# ADCModule.net
KiCad netlist of a schematic drawn in EAGLE
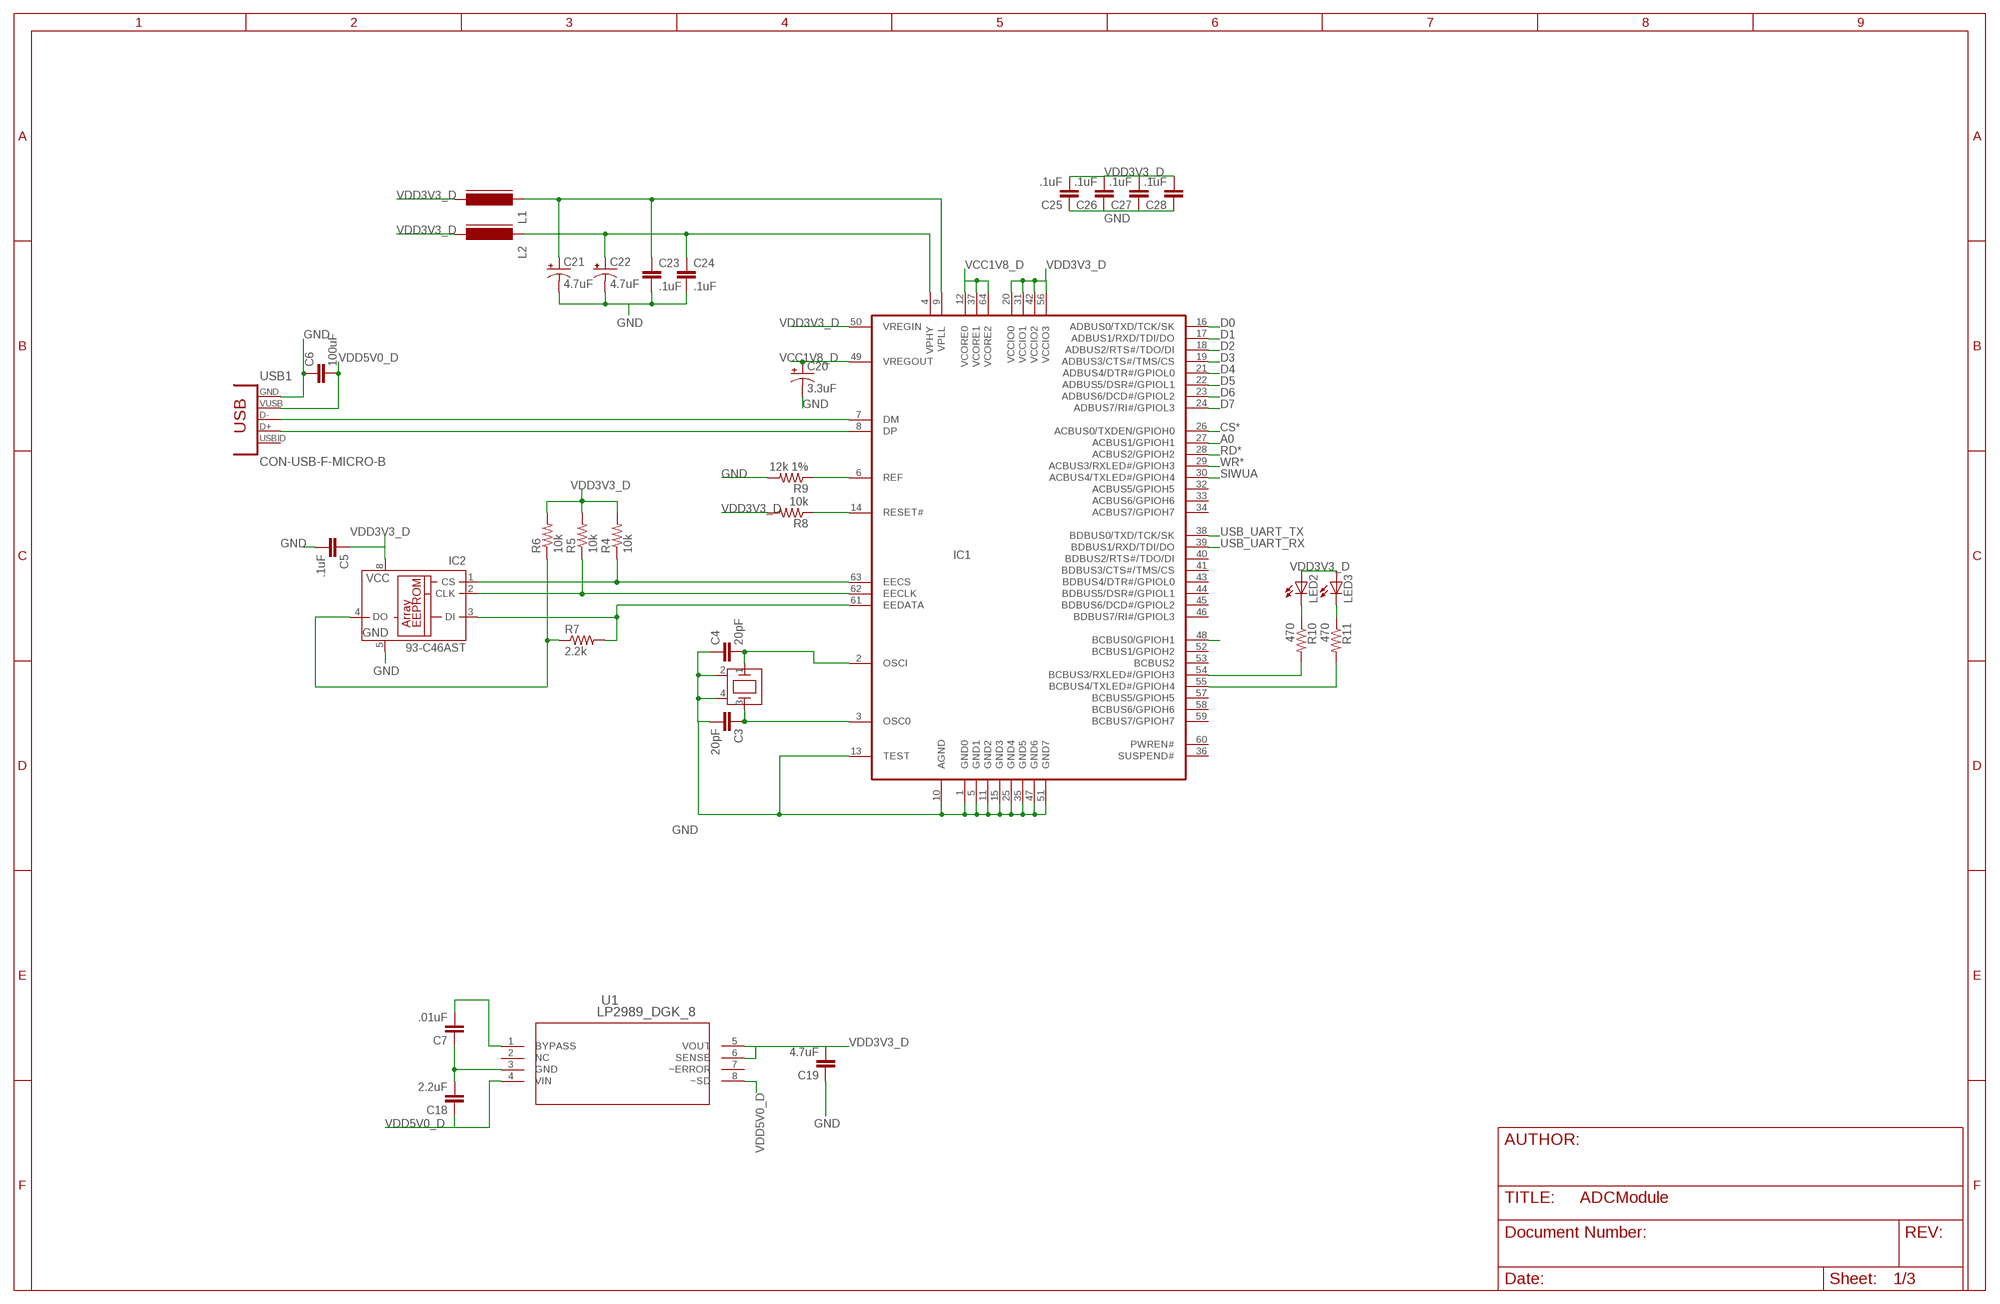
[diagram p0: schematic, sheet 1]
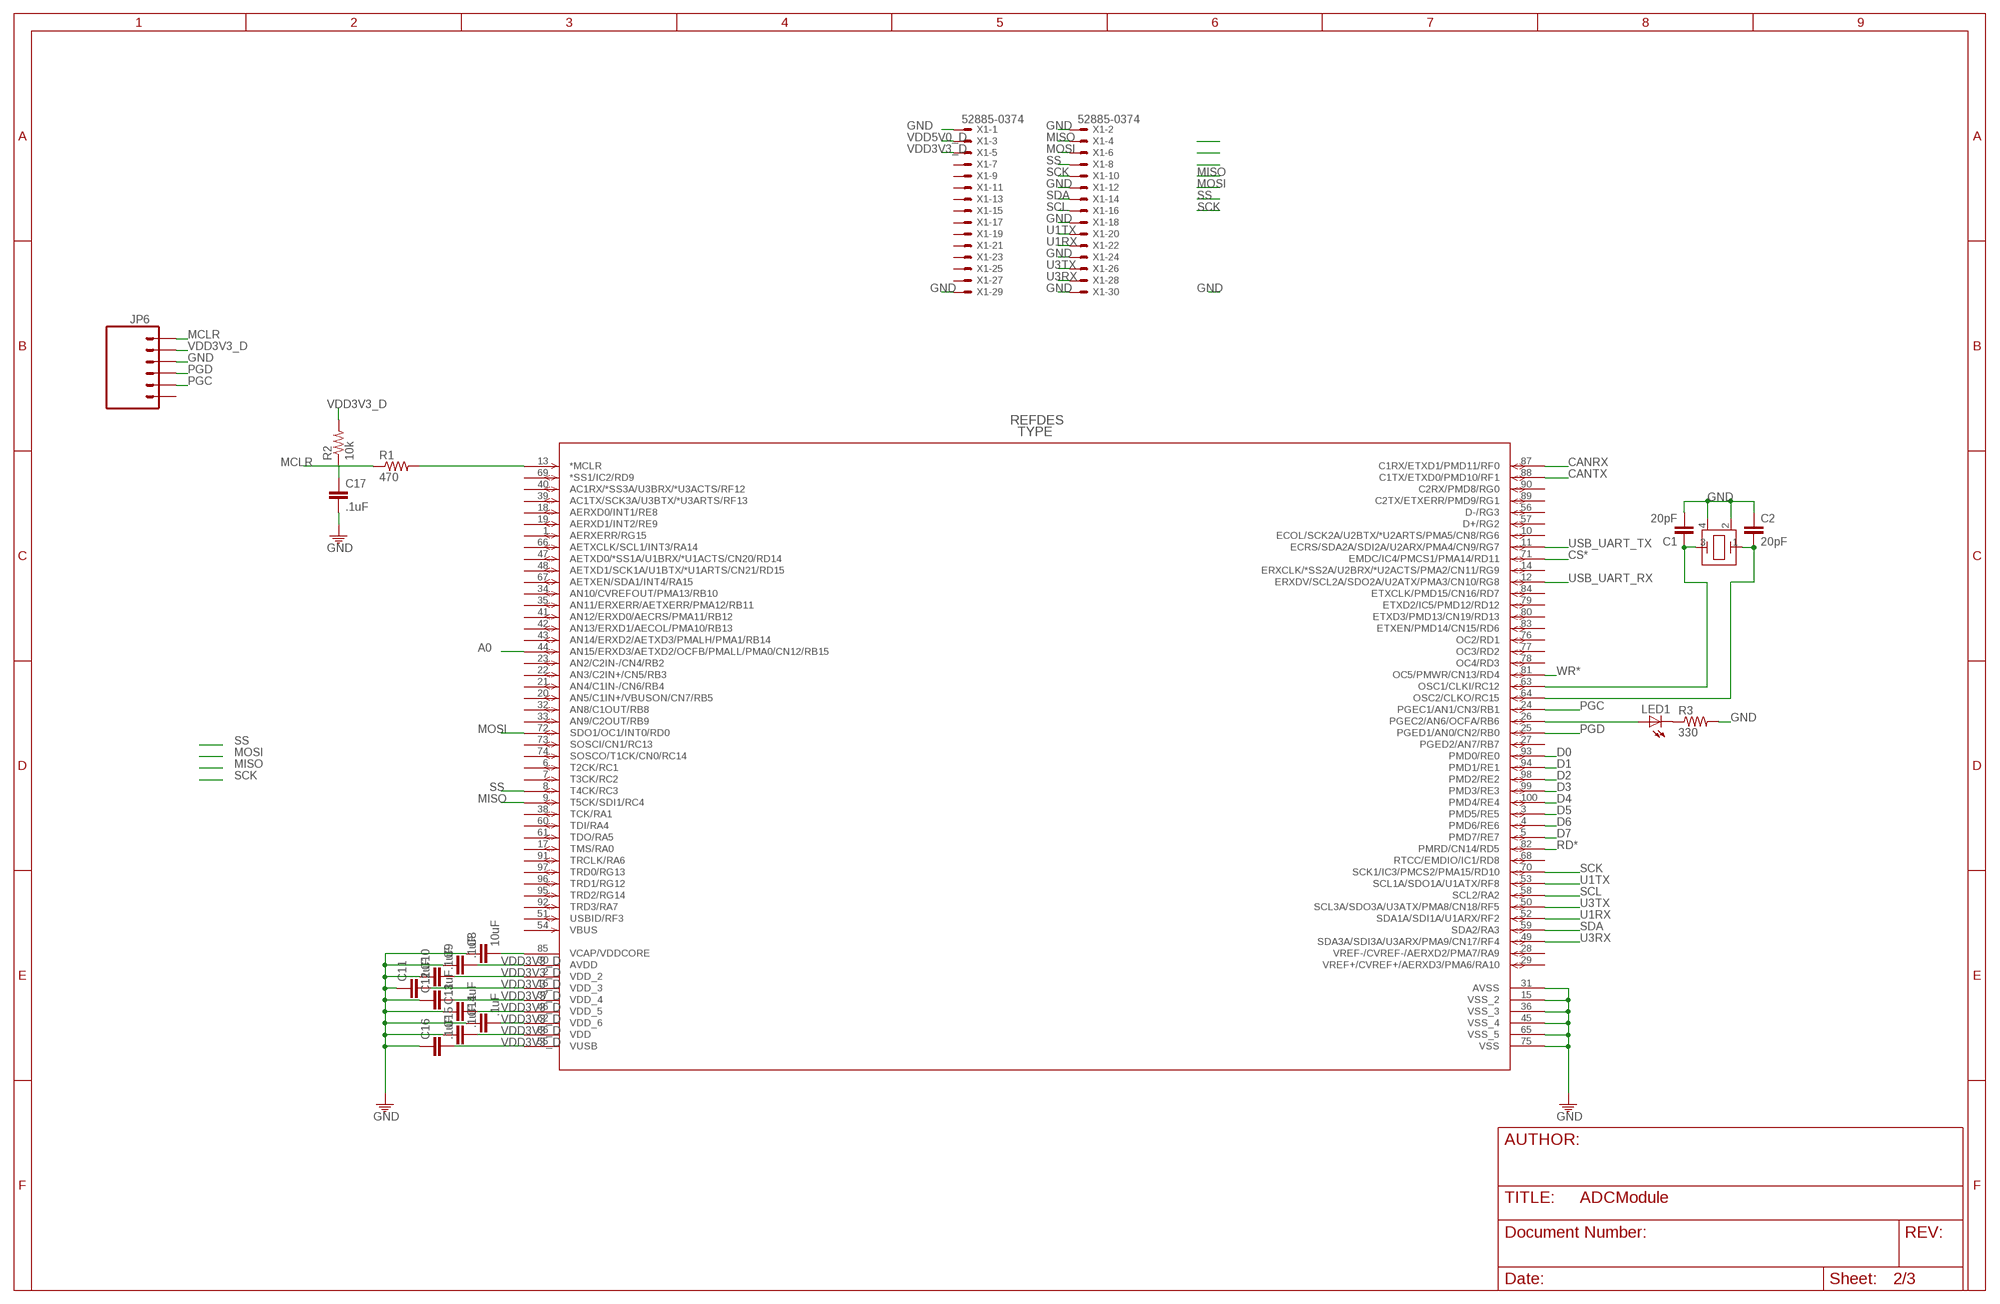
[diagram p1: schematic, sheet 2]
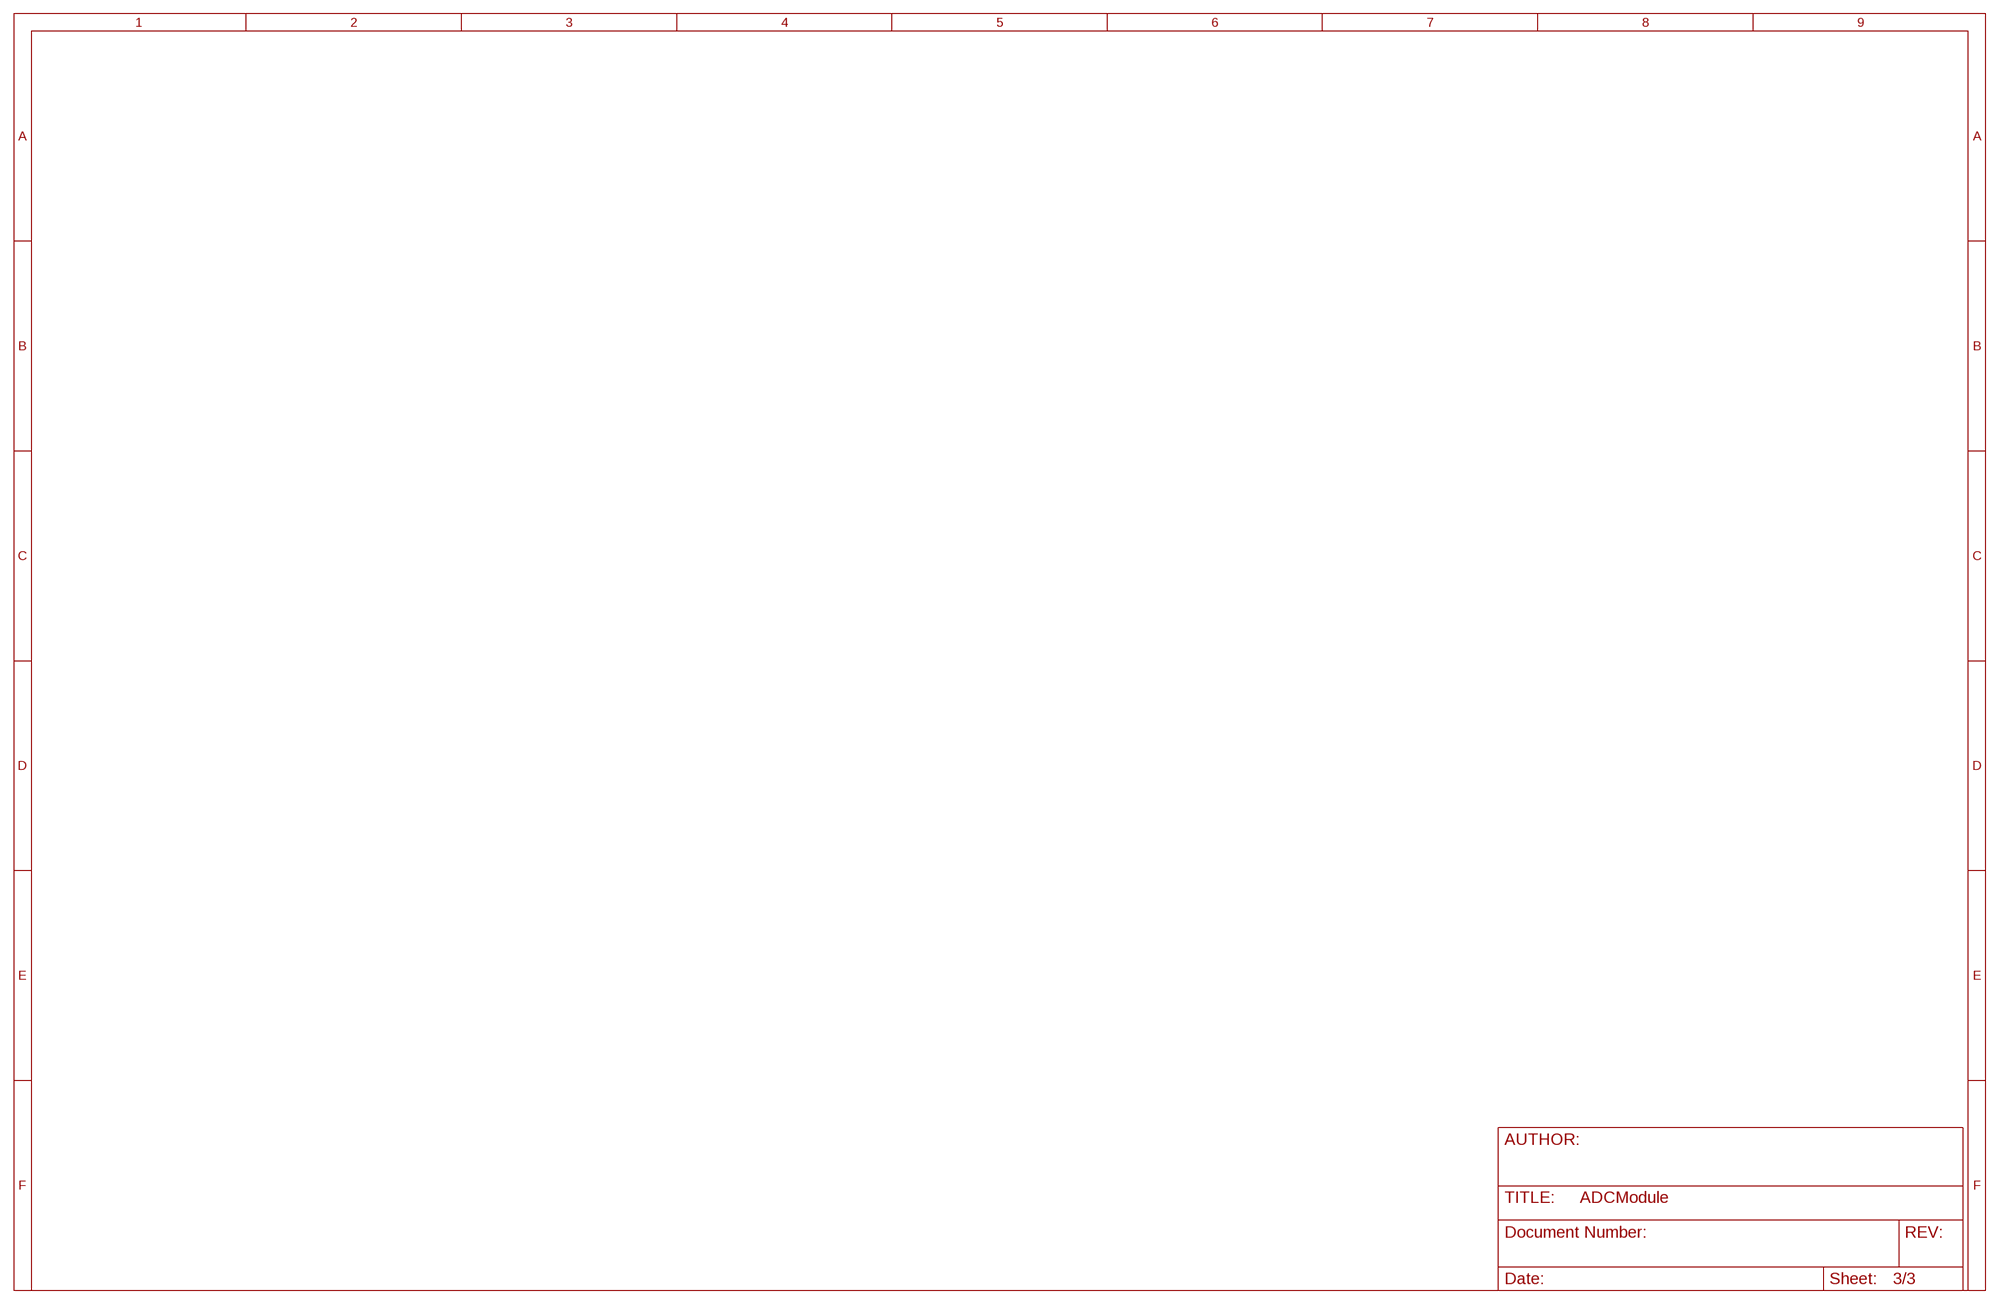
[diagram p2: schematic, sheet 3]

(export (version "E")
  (design (tool "Eeschema 10.0.6"))
  (components
    (comp (ref "C3")
      (value "20pF")
      (footprint "eagle-import:0805")
      (libsource (lib "eagle-import") (part "CAP0805"))
    )
    (comp (ref "C4")
      (value "20pF")
      (footprint "eagle-import:0805")
      (libsource (lib "eagle-import") (part "CAP0805"))
    )
    (comp (ref "C5")
      (value ".1uF")
      (footprint "eagle-import:0805")
      (libsource (lib "eagle-import") (part "CAP0805"))
    )
    (comp (ref "C6")
      (value "100uF")
      (footprint "eagle-import:1206")
      (libsource (lib "eagle-import") (part "CAP1206"))
    )
    (comp (ref "C7")
      (value ".01uF")
      (footprint "eagle-import:0805")
      (libsource (lib "eagle-import") (part "CAP0805"))
    )
    (comp (ref "C18")
      (value "2.2uF")
      (footprint "eagle-import:0805")
      (libsource (lib "eagle-import") (part "CAP0805"))
    )
    (comp (ref "C19")
      (value "4.7uF")
      (footprint "eagle-import:0805")
      (libsource (lib "eagle-import") (part "CAP0805"))
    )
    (comp (ref "C20")
      (value "3.3uF")
      (footprint "eagle-import:EIA3216")
      (libsource (lib "eagle-import") (part "CAP_POL1206"))
    )
    (comp (ref "C21")
      (value "4.7uF")
      (footprint "eagle-import:EIA3216")
      (libsource (lib "eagle-import") (part "CAP_POL1206"))
    )
    (comp (ref "C22")
      (value "4.7uF")
      (footprint "eagle-import:EIA3216")
      (libsource (lib "eagle-import") (part "CAP_POL1206"))
    )
    (comp (ref "C23")
      (value ".1uF")
      (footprint "eagle-import:0805")
      (libsource (lib "eagle-import") (part "CAP0805"))
    )
    (comp (ref "C24")
      (value ".1uF")
      (footprint "eagle-import:0805")
      (libsource (lib "eagle-import") (part "CAP0805"))
    )
    (comp (ref "C25")
      (value ".1uF")
      (footprint "eagle-import:0805")
      (libsource (lib "eagle-import") (part "CAP0805"))
    )
    (comp (ref "C26")
      (value ".1uF")
      (footprint "eagle-import:0805")
      (libsource (lib "eagle-import") (part "CAP0805"))
    )
    (comp (ref "C27")
      (value ".1uF")
      (footprint "eagle-import:0805")
      (libsource (lib "eagle-import") (part "CAP0805"))
    )
    (comp (ref "C28")
      (value ".1uF")
      (footprint "eagle-import:0805")
      (libsource (lib "eagle-import") (part "CAP0805"))
    )
    (comp (ref "IC1")
      (value "IC_FT2232H")
      (footprint "eagle-import:LQFP64")
      (libsource (lib "eagle-import") (part "IC_FT2232H"))
    )
    (comp (ref "IC2")
      (value "93-C46AST")
      (footprint "eagle-import:TSSOP8")
      (fields (field (name "MPN") "CAT93C46YI-G"))
      (libsource (lib "eagle-import") (part "93-STC46A"))
    )
    (comp (ref "L1")
      (value "FERRITE-0805")
      (footprint "eagle-import:FB805")
      (libsource (lib "eagle-import") (part "FERRITE-0805"))
    )
    (comp (ref "L2")
      (value "FERRITE-0805")
      (footprint "eagle-import:FB805")
      (libsource (lib "eagle-import") (part "FERRITE-0805"))
    )
    (comp (ref "LED2")
      (value "LEDCHIP-LED0805")
      (footprint "eagle-import:CHIP-LED0805")
      (libsource (lib "eagle-import") (part "LEDCHIP-LED0805"))
    )
    (comp (ref "LED3")
      (value "LEDCHIP-LED0805")
      (footprint "eagle-import:CHIP-LED0805")
      (libsource (lib "eagle-import") (part "LEDCHIP-LED0805"))
    )
    (comp (ref "R4")
      (value "10k")
      (footprint "eagle-import:0805")
      (libsource (lib "eagle-import") (part "RESISTOR0805-RES"))
    )
    (comp (ref "R5")
      (value "10k")
      (footprint "eagle-import:0805")
      (libsource (lib "eagle-import") (part "RESISTOR0805-RES"))
    )
    (comp (ref "R6")
      (value "10k")
      (footprint "eagle-import:0805")
      (libsource (lib "eagle-import") (part "RESISTOR0805-RES"))
    )
    (comp (ref "R7")
      (value "2.2k")
      (footprint "eagle-import:0805")
      (libsource (lib "eagle-import") (part "RESISTOR0805-RES"))
    )
    (comp (ref "R8")
      (value "10k")
      (footprint "eagle-import:0805")
      (libsource (lib "eagle-import") (part "RESISTOR0805-RES"))
    )
    (comp (ref "R9")
      (value "12k 1%")
      (footprint "eagle-import:0805")
      (libsource (lib "eagle-import") (part "RESISTOR0805-RES"))
    )
    (comp (ref "R10")
      (value "470")
      (footprint "eagle-import:0805")
      (libsource (lib "eagle-import") (part "RESISTOR0805-RES"))
    )
    (comp (ref "R11")
      (value "470")
      (footprint "eagle-import:0805")
      (libsource (lib "eagle-import") (part "RESISTOR0805-RES"))
    )
    (comp (ref "U$3")
      (value "7M-12.000MEEQ-T")
      (footprint "eagle-import:7M-CRYSTAL")
      (libsource (lib "eagle-import") (part "7M-12.000MEEQ-T"))
    )
    (comp (ref "U1")
      (value "LP2989_DGK_8")
      (footprint "eagle-import:MUA08A")
      (fields (field (name "PARTNUMBER") "LP2989AIMM-25"))
      (libsource (lib "eagle-import") (part "LP2989_DGK_8"))
    )
    (comp (ref "USB1")
      (value "CON-USB-F-MICRO-B")
      (footprint "eagle-import:CONN_USB_MICRO-B")
      (libsource (lib "eagle-import") (part "CON-USB-F-MICRO-B"))
    )
    (comp (ref "C1")
      (value "20pF")
      (footprint "eagle-import:0805")
      (libsource (lib "eagle-import") (part "CAP0805"))
    )
    (comp (ref "C2")
      (value "20pF")
      (footprint "eagle-import:0805")
      (libsource (lib "eagle-import") (part "CAP0805"))
    )
    (comp (ref "C8")
      (value "10uF")
      (footprint "eagle-import:0805")
      (libsource (lib "eagle-import") (part "CAP0805"))
    )
    (comp (ref "C9")
      (value ".1uF")
      (footprint "eagle-import:0805")
      (libsource (lib "eagle-import") (part "CAP0805"))
    )
    (comp (ref "C10")
      (value ".1uF")
      (footprint "eagle-import:0805")
      (libsource (lib "eagle-import") (part "CAP0805"))
    )
    (comp (ref "C11")
      (value ".1uF")
      (footprint "eagle-import:0805")
      (libsource (lib "eagle-import") (part "CAP0805"))
    )
    (comp (ref "C12")
      (value ".1uF")
      (footprint "eagle-import:0805")
      (libsource (lib "eagle-import") (part "CAP0805"))
    )
    (comp (ref "C13")
      (value ".1uF")
      (footprint "eagle-import:0805")
      (libsource (lib "eagle-import") (part "CAP0805"))
    )
    (comp (ref "C14")
      (value ".1uF")
      (footprint "eagle-import:0805")
      (libsource (lib "eagle-import") (part "CAP0805"))
    )
    (comp (ref "C15")
      (value ".1uF")
      (footprint "eagle-import:0805")
      (libsource (lib "eagle-import") (part "CAP0805"))
    )
    (comp (ref "C16")
      (value ".1uF")
      (footprint "eagle-import:0805")
      (libsource (lib "eagle-import") (part "CAP0805"))
    )
    (comp (ref "C17")
      (value ".1uF")
      (footprint "eagle-import:0805")
      (libsource (lib "eagle-import") (part "CAP0805"))
    )
    (comp (ref "JP6")
      (value "M06SIP_LOCK")
      (footprint "eagle-import:1X06-SIP_LOCK")
      (libsource (lib "eagle-import") (part "M06SIP_LOCK"))
    )
    (comp (ref "LED1")
      (value "LED0805")
      (footprint "eagle-import:LED-0805")
      (libsource (lib "eagle-import") (part "LED0805"))
    )
    (comp (ref "R1")
      (value "470")
      (footprint "eagle-import:0805")
      (libsource (lib "eagle-import") (part "RESISTOR0805-RES"))
    )
    (comp (ref "R2")
      (value "10k")
      (footprint "eagle-import:0805")
      (libsource (lib "eagle-import") (part "RESISTOR0805-RES"))
    )
    (comp (ref "R3")
      (value "330")
      (footprint "eagle-import:0805")
      (libsource (lib "eagle-import") (part "RESISTOR0805-RES"))
    )
    (comp (ref "U$1")
      (value "PIC32MX795F512L-")
      (footprint "eagle-import:TQFP100_12X12MC")
      (libsource (lib "eagle-import") (part "PIC32MX795F512L-"))
    )
    (comp (ref "U$2")
      (value "ABM3B-8.000MHZ-10-1-U-T")
      (footprint "eagle-import:ABM3B")
      (libsource (lib "eagle-import") (part "ABM3B-8.000MHZ-10-1-U-T"))
    )
    (comp (ref "X1")
      (value "52885-0374")
      (footprint "eagle-import:52885-0374")
      (fields (field (name "MPN") "52760-0379"))
      (libsource (lib "eagle-import") (part "52885-0374"))
    )
  )
  (nets
    (net (code "1") (name "A0") (class "Default")
      (node (ref "IC1") (pin "27") (pinfunction "ACBUS1/GPIOH1_27") (pintype "bidirectional"))
      (node (ref "U$1") (pin "44") (pinfunction "AN15/ERXD3/AETXD2/OCFB/PMALL/PMA0/CN12/RB15_44") (pintype "passive"))
    )
    (net (code "2") (name "CANRX") (class "Default")
      (node (ref "U$1") (pin "87") (pinfunction "C1RX/ETXD1/PMD11/RF0_87") (pintype "passive"))
    )
    (net (code "3") (name "CANTX") (class "Default")
      (node (ref "U$1") (pin "88") (pinfunction "C1TX/ETXD0/PMD10/RF1_88") (pintype "passive"))
    )
    (net (code "4") (name "CS*") (class "Default")
      (node (ref "IC1") (pin "26") (pinfunction "ACBUS0/TXDEN/GPIOH0_26") (pintype "bidirectional"))
      (node (ref "U$1") (pin "71") (pinfunction "EMDC/IC4/PMCS1/PMA14/RD11_71") (pintype "passive"))
    )
    (net (code "5") (name "D0") (class "Default")
      (node (ref "IC1") (pin "16") (pinfunction "ADBUS0/TXD/TCK/SK_16") (pintype "bidirectional"))
      (node (ref "U$1") (pin "93") (pinfunction "PMD0/RE0_93") (pintype "passive"))
    )
    (net (code "6") (name "D1") (class "Default")
      (node (ref "IC1") (pin "17") (pinfunction "ADBUS1/RXD/TDI/DO_17") (pintype "bidirectional"))
      (node (ref "U$1") (pin "94") (pinfunction "PMD1/RE1_94") (pintype "passive"))
    )
    (net (code "7") (name "D2") (class "Default")
      (node (ref "IC1") (pin "18") (pinfunction "ADBUS2/RTS#/TDO/DI_18") (pintype "bidirectional"))
      (node (ref "U$1") (pin "98") (pinfunction "PMD2/RE2_98") (pintype "passive"))
    )
    (net (code "8") (name "D3") (class "Default")
      (node (ref "IC1") (pin "19") (pinfunction "ADBUS3/CTS#/TMS/CS_19") (pintype "bidirectional"))
      (node (ref "U$1") (pin "99") (pinfunction "PMD3/RE3_99") (pintype "passive"))
    )
    (net (code "9") (name "D4") (class "Default")
      (node (ref "IC1") (pin "21") (pinfunction "ADBUS4/DTR#/GPIOL0_21") (pintype "bidirectional"))
      (node (ref "U$1") (pin "100") (pinfunction "PMD4/RE4_100") (pintype "passive"))
    )
    (net (code "10") (name "D5") (class "Default")
      (node (ref "IC1") (pin "22") (pinfunction "ADBUS5/DSR#/GPIOL1_22") (pintype "bidirectional"))
      (node (ref "U$1") (pin "3") (pinfunction "PMD5/RE5_3") (pintype "passive"))
    )
    (net (code "11") (name "D6") (class "Default")
      (node (ref "IC1") (pin "23") (pinfunction "ADBUS6/DCD#/GPIOL2_23") (pintype "bidirectional"))
      (node (ref "U$1") (pin "4") (pinfunction "PMD6/RE6_4") (pintype "passive"))
    )
    (net (code "12") (name "D7") (class "Default")
      (node (ref "IC1") (pin "24") (pinfunction "ADBUS7/RI#/GPIOL3_24") (pintype "bidirectional"))
      (node (ref "U$1") (pin "5") (pinfunction "PMD7/RE7_5") (pintype "passive"))
    )
    (net (code "13") (name "GND") (class "Default")
      (node (ref "C1") (pin "2") (pinfunction "2_2") (pintype "passive"))
      (node (ref "C10") (pin "1") (pinfunction "1_1") (pintype "passive"))
      (node (ref "C11") (pin "1") (pinfunction "1_1") (pintype "passive"))
      (node (ref "C12") (pin "1") (pinfunction "1_1") (pintype "passive"))
      (node (ref "C13") (pin "1") (pinfunction "1_1") (pintype "passive"))
      (node (ref "C14") (pin "1") (pinfunction "1_1") (pintype "passive"))
      (node (ref "C15") (pin "1") (pinfunction "1_1") (pintype "passive"))
      (node (ref "C16") (pin "1") (pinfunction "1_1") (pintype "passive"))
      (node (ref "C17") (pin "2") (pinfunction "2_2") (pintype "passive"))
      (node (ref "C18") (pin "2") (pinfunction "2_2") (pintype "passive"))
      (node (ref "C19") (pin "1") (pinfunction "1_1") (pintype "passive"))
      (node (ref "C2") (pin "1") (pinfunction "1_1") (pintype "passive"))
      (node (ref "C20") (pin "C") (pinfunction "-_C") (pintype "passive"))
      (node (ref "C21") (pin "C") (pinfunction "-_C") (pintype "passive"))
      (node (ref "C22") (pin "C") (pinfunction "-_C") (pintype "passive"))
      (node (ref "C23") (pin "2") (pinfunction "2_2") (pintype "passive"))
      (node (ref "C24") (pin "2") (pinfunction "2_2") (pintype "passive"))
      (node (ref "C25") (pin "1") (pinfunction "1_1") (pintype "passive"))
      (node (ref "C26") (pin "1") (pinfunction "1_1") (pintype "passive"))
      (node (ref "C27") (pin "1") (pinfunction "1_1") (pintype "passive"))
      (node (ref "C28") (pin "1") (pinfunction "1_1") (pintype "passive"))
      (node (ref "C3") (pin "2") (pinfunction "2_2") (pintype "passive"))
      (node (ref "C4") (pin "1") (pinfunction "1_1") (pintype "passive"))
      (node (ref "C5") (pin "2") (pinfunction "2_2") (pintype "passive"))
      (node (ref "C6") (pin "1") (pinfunction "1_1") (pintype "passive"))
      (node (ref "C7") (pin "1") (pinfunction "1_1") (pintype "passive"))
      (node (ref "C8") (pin "1") (pinfunction "1_1") (pintype "passive"))
      (node (ref "C9") (pin "1") (pinfunction "1_1") (pintype "passive"))
      (node (ref "IC1") (pin "1") (pinfunction "GND0_1") (pintype "bidirectional"))
      (node (ref "IC1") (pin "10") (pinfunction "AGND_10") (pintype "bidirectional"))
      (node (ref "IC1") (pin "11") (pinfunction "GND2_11") (pintype "bidirectional"))
      (node (ref "IC1") (pin "13") (pinfunction "TEST_13") (pintype "bidirectional"))
      (node (ref "IC1") (pin "15") (pinfunction "GND3_15") (pintype "bidirectional"))
      (node (ref "IC1") (pin "25") (pinfunction "GND4_25") (pintype "bidirectional"))
      (node (ref "IC1") (pin "35") (pinfunction "GND5_35") (pintype "bidirectional"))
      (node (ref "IC1") (pin "47") (pinfunction "GND6_47") (pintype "bidirectional"))
      (node (ref "IC1") (pin "5") (pinfunction "GND1_5") (pintype "bidirectional"))
      (node (ref "IC1") (pin "51") (pinfunction "GND7_51") (pintype "bidirectional"))
      (node (ref "IC2") (pin "5") (pinfunction "GND_5") (pintype "power_in"))
      (node (ref "JP6") (pin "3") (pinfunction "3_3") (pintype "passive"))
      (node (ref "R3") (pin "2") (pinfunction "2_2") (pintype "passive"))
      (node (ref "R9") (pin "2") (pinfunction "2_2") (pintype "passive"))
      (node (ref "U$1") (pin "15") (pinfunction "VSS_2_15") (pintype "passive"))
      (node (ref "U$1") (pin "31") (pinfunction "AVSS_31") (pintype "passive"))
      (node (ref "U$1") (pin "36") (pinfunction "VSS_3_36") (pintype "passive"))
      (node (ref "U$1") (pin "45") (pinfunction "VSS_4_45") (pintype "passive"))
      (node (ref "U$1") (pin "65") (pinfunction "VSS_5_65") (pintype "passive"))
      (node (ref "U$1") (pin "75") (pinfunction "VSS_75") (pintype "passive"))
      (node (ref "U$2") (pin "2") (pinfunction "GND1_2") (pintype "bidirectional"))
      (node (ref "U$2") (pin "4") (pinfunction "GND2_4") (pintype "bidirectional"))
      (node (ref "U$3") (pin "2") (pinfunction "GND1_2") (pintype "bidirectional"))
      (node (ref "U$3") (pin "4") (pinfunction "GND2_4") (pintype "bidirectional"))
      (node (ref "U1") (pin "3") (pinfunction "GND_3") (pintype "passive"))
      (node (ref "USB1") (pin "P5") (pinfunction "GND_P5") (pintype "bidirectional"))
      (node (ref "X1") (pin "1") (pinfunction "S_1") (pintype "passive"))
      (node (ref "X1") (pin "12") (pinfunction "S_12") (pintype "passive"))
      (node (ref "X1") (pin "18") (pinfunction "S_18") (pintype "passive"))
      (node (ref "X1") (pin "2") (pinfunction "S_2") (pintype "passive"))
      (node (ref "X1") (pin "24") (pinfunction "S_24") (pintype "passive"))
      (node (ref "X1") (pin "29") (pinfunction "S_29") (pintype "passive"))
      (node (ref "X1") (pin "30") (pinfunction "S_30") (pintype "passive"))
    )
    (net (code "14") (name "MCLR") (class "Default")
      (node (ref "C17") (pin "1") (pinfunction "1_1") (pintype "passive"))
      (node (ref "JP6") (pin "1") (pinfunction "1_1") (pintype "passive"))
      (node (ref "R1") (pin "1") (pinfunction "1_1") (pintype "passive"))
      (node (ref "R2") (pin "1") (pinfunction "1_1") (pintype "passive"))
    )
    (net (code "15") (name "MISO") (class "Default")
      (node (ref "U$1") (pin "9") (pinfunction "T5CK/SDI1/RC4_9") (pintype "passive"))
      (node (ref "X1") (pin "4") (pinfunction "S_4") (pintype "passive"))
    )
    (net (code "16") (name "MOSI") (class "Default")
      (node (ref "U$1") (pin "72") (pinfunction "SDO1/OC1/INT0/RD0_72") (pintype "passive"))
      (node (ref "X1") (pin "6") (pinfunction "S_6") (pintype "passive"))
    )
    (net (code "17") (name "Net-(C21-+)") (class "Default")
      (node (ref "C21") (pin "A") (pinfunction "+_A") (pintype "passive"))
      (node (ref "C23") (pin "1") (pinfunction "1_1") (pintype "passive"))
      (node (ref "IC1") (pin "9") (pinfunction "VPLL_9") (pintype "bidirectional"))
      (node (ref "L1") (pin "1") (pinfunction "1_1") (pintype "passive"))
    )
    (net (code "18") (name "Net-(C22-+)") (class "Default")
      (node (ref "C22") (pin "A") (pinfunction "+_A") (pintype "passive"))
      (node (ref "C24") (pin "1") (pinfunction "1_1") (pintype "passive"))
      (node (ref "IC1") (pin "4") (pinfunction "VPHY_4") (pintype "bidirectional"))
      (node (ref "L2") (pin "1") (pinfunction "1_1") (pintype "passive"))
    )
    (net (code "19") (name "Net-(IC1-BCBUS3{slash}RXLED#{slash}GPIOH3)") (class "Default")
      (node (ref "IC1") (pin "54") (pinfunction "BCBUS3/RXLED#/GPIOH3_54") (pintype "bidirectional"))
      (node (ref "R10") (pin "2") (pinfunction "2_2") (pintype "passive"))
    )
    (net (code "20") (name "Net-(IC1-BCBUS4{slash}TXLED#{slash}GPIOH4)") (class "Default")
      (node (ref "IC1") (pin "55") (pinfunction "BCBUS4/TXLED#/GPIOH4_55") (pintype "bidirectional"))
      (node (ref "R11") (pin "2") (pinfunction "2_2") (pintype "passive"))
    )
    (net (code "21") (name "Net-(IC1-DM)") (class "Default")
      (node (ref "IC1") (pin "7") (pinfunction "DM_7") (pintype "bidirectional"))
      (node (ref "USB1") (pin "P2") (pinfunction "D-_P2") (pintype "bidirectional"))
    )
    (net (code "22") (name "Net-(IC1-DP)") (class "Default")
      (node (ref "IC1") (pin "8") (pinfunction "DP_8") (pintype "bidirectional"))
      (node (ref "USB1") (pin "P3") (pinfunction "D+_P3") (pintype "bidirectional"))
    )
    (net (code "23") (name "Net-(IC1-EECLK)") (class "Default")
      (node (ref "IC1") (pin "62") (pinfunction "EECLK_62") (pintype "bidirectional"))
      (node (ref "IC2") (pin "2") (pinfunction "CLK_2") (pintype "input"))
      (node (ref "R5") (pin "1") (pinfunction "1_1") (pintype "passive"))
    )
    (net (code "24") (name "Net-(IC1-EECS)") (class "Default")
      (node (ref "IC1") (pin "63") (pinfunction "EECS_63") (pintype "bidirectional"))
      (node (ref "IC2") (pin "1") (pinfunction "CS_1") (pintype "input"))
      (node (ref "R4") (pin "1") (pinfunction "1_1") (pintype "passive"))
    )
    (net (code "25") (name "Net-(IC1-EEDATA)") (class "Default")
      (node (ref "IC1") (pin "61") (pinfunction "EEDATA_61") (pintype "bidirectional"))
      (node (ref "IC2") (pin "3") (pinfunction "DI_3") (pintype "input"))
      (node (ref "R7") (pin "2") (pinfunction "2_2") (pintype "passive"))
    )
    (net (code "26") (name "Net-(IC1-OSC0)") (class "Default")
      (node (ref "C3") (pin "1") (pinfunction "1_1") (pintype "passive"))
      (node (ref "IC1") (pin "3") (pinfunction "OSC0_3") (pintype "bidirectional"))
      (node (ref "U$3") (pin "3") (pinfunction "OSC2_3") (pintype "bidirectional"))
    )
    (net (code "27") (name "Net-(IC1-OSCI)") (class "Default")
      (node (ref "C4") (pin "2") (pinfunction "2_2") (pintype "passive"))
      (node (ref "IC1") (pin "2") (pinfunction "OSCI_2") (pintype "bidirectional"))
      (node (ref "U$3") (pin "1") (pinfunction "OSC1_1") (pintype "bidirectional"))
    )
    (net (code "28") (name "Net-(IC1-REF)") (class "Default")
      (node (ref "IC1") (pin "6") (pinfunction "REF_6") (pintype "bidirectional"))
      (node (ref "R9") (pin "1") (pinfunction "1_1") (pintype "passive"))
    )
    (net (code "29") (name "Net-(IC1-RESET#)") (class "Default")
      (node (ref "IC1") (pin "14") (pinfunction "RESET#_14") (pintype "bidirectional"))
      (node (ref "R8") (pin "1") (pinfunction "1_1") (pintype "passive"))
    )
    (net (code "30") (name "Net-(IC2-DO)") (class "Default")
      (node (ref "IC2") (pin "4") (pinfunction "DO_4") (pintype "tri_state"))
      (node (ref "R6") (pin "1") (pinfunction "1_1") (pintype "passive"))
      (node (ref "R7") (pin "1") (pinfunction "1_1") (pintype "passive"))
    )
    (net (code "31") (name "Net-(LED1-A)") (class "Default")
      (node (ref "LED1") (pin "1") (pinfunction "A_1") (pintype "passive"))
      (node (ref "U$1") (pin "26") (pinfunction "PGEC2/AN6/OCFA/RB6_26") (pintype "passive"))
    )
    (net (code "32") (name "Net-(LED1-C)") (class "Default")
      (node (ref "LED1") (pin "2") (pinfunction "C_2") (pintype "passive"))
      (node (ref "R3") (pin "1") (pinfunction "1_1") (pintype "passive"))
    )
    (net (code "33") (name "Net-(LED2-PadC)") (class "Default")
      (node (ref "LED2") (pin "C") (pinfunction "C_C") (pintype "passive"))
      (node (ref "R10") (pin "1") (pinfunction "1_1") (pintype "passive"))
    )
    (net (code "34") (name "Net-(LED3-PadC)") (class "Default")
      (node (ref "LED3") (pin "C") (pinfunction "C_C") (pintype "passive"))
      (node (ref "R11") (pin "1") (pinfunction "1_1") (pintype "passive"))
    )
    (net (code "35") (name "Net-(U$1-*MCLR)") (class "Default")
      (node (ref "R1") (pin "2") (pinfunction "2_2") (pintype "passive"))
      (node (ref "U$1") (pin "13") (pinfunction "*MCLR_13") (pintype "passive"))
    )
    (net (code "36") (name "Net-(U$1-OSC1{slash}CLKI{slash}RC12)") (class "Default")
      (node (ref "C1") (pin "1") (pinfunction "1_1") (pintype "passive"))
      (node (ref "U$1") (pin "63") (pinfunction "OSC1/CLKI/RC12_63") (pintype "passive"))
      (node (ref "U$2") (pin "3") (pinfunction "OSC2_3") (pintype "bidirectional"))
    )
    (net (code "37") (name "Net-(U$1-OSC2{slash}CLKO{slash}RC15)") (class "Default")
      (node (ref "C2") (pin "2") (pinfunction "2_2") (pintype "passive"))
      (node (ref "U$1") (pin "64") (pinfunction "OSC2/CLKO/RC15_64") (pintype "passive"))
      (node (ref "U$2") (pin "1") (pinfunction "OSC1_1") (pintype "bidirectional"))
    )
    (net (code "38") (name "Net-(U$1-VCAP{slash}VDDCORE)") (class "Default")
      (node (ref "C8") (pin "2") (pinfunction "2_2") (pintype "passive"))
      (node (ref "U$1") (pin "85") (pinfunction "VCAP/VDDCORE_85") (pintype "passive"))
    )
    (net (code "39") (name "Net-(U1-BYPASS)") (class "Default")
      (node (ref "C7") (pin "2") (pinfunction "2_2") (pintype "passive"))
      (node (ref "U1") (pin "1") (pinfunction "BYPASS_1") (pintype "passive"))
    )
    (net (code "40") (name "PGC") (class "Default")
      (node (ref "JP6") (pin "5") (pinfunction "5_5") (pintype "passive"))
      (node (ref "U$1") (pin "24") (pinfunction "PGEC1/AN1/CN3/RB1_24") (pintype "passive"))
    )
    (net (code "41") (name "PGD") (class "Default")
      (node (ref "JP6") (pin "4") (pinfunction "4_4") (pintype "passive"))
      (node (ref "U$1") (pin "25") (pinfunction "PGED1/AN0/CN2/RB0_25") (pintype "passive"))
    )
    (net (code "42") (name "RD*") (class "Default")
      (node (ref "IC1") (pin "28") (pinfunction "ACBUS2/GPIOH2_28") (pintype "bidirectional"))
      (node (ref "U$1") (pin "82") (pinfunction "PMRD/CN14/RD5_82") (pintype "passive"))
    )
    (net (code "43") (name "SCK") (class "Default")
      (node (ref "U$1") (pin "70") (pinfunction "SCK1/IC3/PMCS2/PMA15/RD10_70") (pintype "passive"))
      (node (ref "X1") (pin "10") (pinfunction "S_10") (pintype "passive"))
    )
    (net (code "44") (name "SCL") (class "Default")
      (node (ref "U$1") (pin "58") (pinfunction "SCL2/RA2_58") (pintype "passive"))
      (node (ref "X1") (pin "16") (pinfunction "S_16") (pintype "passive"))
    )
    (net (code "45") (name "SDA") (class "Default")
      (node (ref "U$1") (pin "59") (pinfunction "SDA2/RA3_59") (pintype "passive"))
      (node (ref "X1") (pin "14") (pinfunction "S_14") (pintype "passive"))
    )
    (net (code "46") (name "SIWUA") (class "Default")
      (node (ref "IC1") (pin "30") (pinfunction "ACBUS4/TXLED#/GPIOH4_30") (pintype "bidirectional"))
    )
    (net (code "47") (name "SS") (class "Default")
      (node (ref "U$1") (pin "8") (pinfunction "T4CK/RC3_8") (pintype "passive"))
      (node (ref "X1") (pin "8") (pinfunction "S_8") (pintype "passive"))
    )
    (net (code "48") (name "U1RX") (class "Default")
      (node (ref "U$1") (pin "52") (pinfunction "SDA1A/SDI1A/U1ARX/RF2_52") (pintype "passive"))
      (node (ref "X1") (pin "22") (pinfunction "S_22") (pintype "passive"))
    )
    (net (code "49") (name "U1TX") (class "Default")
      (node (ref "U$1") (pin "53") (pinfunction "SCL1A/SDO1A/U1ATX/RF8_53") (pintype "passive"))
      (node (ref "X1") (pin "20") (pinfunction "S_20") (pintype "passive"))
    )
    (net (code "50") (name "U3RX") (class "Default")
      (node (ref "U$1") (pin "49") (pinfunction "SDA3A/SDI3A/U3ARX/PMA9/CN17/RF4_49") (pintype "passive"))
      (node (ref "X1") (pin "28") (pinfunction "S_28") (pintype "passive"))
    )
    (net (code "51") (name "U3TX") (class "Default")
      (node (ref "U$1") (pin "50") (pinfunction "SCL3A/SDO3A/U3ATX/PMA8/CN18/RF5_50") (pintype "passive"))
      (node (ref "X1") (pin "26") (pinfunction "S_26") (pintype "passive"))
    )
    (net (code "52") (name "USB_UART_RX") (class "Default")
      (node (ref "IC1") (pin "39") (pinfunction "BDBUS1/RXD/TDI/DO_39") (pintype "bidirectional"))
      (node (ref "U$1") (pin "12") (pinfunction "ERXDV/SCL2A/SDO2A/U2ATX/PMA3/CN10/RG8_12") (pintype "passive"))
    )
    (net (code "53") (name "USB_UART_TX") (class "Default")
      (node (ref "IC1") (pin "38") (pinfunction "BDBUS0/TXD/TCK/SK_38") (pintype "bidirectional"))
      (node (ref "U$1") (pin "11") (pinfunction "ECRS/SDA2A/SDI2A/U2ARX/PMA4/CN9/RG7_11") (pintype "passive"))
    )
    (net (code "54") (name "VCC1V8_D") (class "Default")
      (node (ref "C20") (pin "A") (pinfunction "+_A") (pintype "passive"))
      (node (ref "IC1") (pin "12") (pinfunction "VCORE0_12") (pintype "bidirectional"))
      (node (ref "IC1") (pin "37") (pinfunction "VCORE1_37") (pintype "bidirectional"))
      (node (ref "IC1") (pin "49") (pinfunction "VREGOUT_49") (pintype "bidirectional"))
      (node (ref "IC1") (pin "64") (pinfunction "VCORE2_64") (pintype "bidirectional"))
    )
    (net (code "55") (name "VDD3V3_D") (class "Default")
      (node (ref "C10") (pin "2") (pinfunction "2_2") (pintype "passive"))
      (node (ref "C11") (pin "2") (pinfunction "2_2") (pintype "passive"))
      (node (ref "C12") (pin "2") (pinfunction "2_2") (pintype "passive"))
      (node (ref "C13") (pin "2") (pinfunction "2_2") (pintype "passive"))
      (node (ref "C14") (pin "2") (pinfunction "2_2") (pintype "passive"))
      (node (ref "C15") (pin "2") (pinfunction "2_2") (pintype "passive"))
      (node (ref "C16") (pin "2") (pinfunction "2_2") (pintype "passive"))
      (node (ref "C19") (pin "2") (pinfunction "2_2") (pintype "passive"))
      (node (ref "C25") (pin "2") (pinfunction "2_2") (pintype "passive"))
      (node (ref "C26") (pin "2") (pinfunction "2_2") (pintype "passive"))
      (node (ref "C27") (pin "2") (pinfunction "2_2") (pintype "passive"))
      (node (ref "C28") (pin "2") (pinfunction "2_2") (pintype "passive"))
      (node (ref "C5") (pin "1") (pinfunction "1_1") (pintype "passive"))
      (node (ref "C9") (pin "2") (pinfunction "2_2") (pintype "passive"))
      (node (ref "IC1") (pin "20") (pinfunction "VCCIO0_20") (pintype "bidirectional"))
      (node (ref "IC1") (pin "31") (pinfunction "VCCIO1_31") (pintype "bidirectional"))
      (node (ref "IC1") (pin "42") (pinfunction "VCCIO2_42") (pintype "bidirectional"))
      (node (ref "IC1") (pin "50") (pinfunction "VREGIN_50") (pintype "bidirectional"))
      (node (ref "IC1") (pin "56") (pinfunction "VCCIO3_56") (pintype "bidirectional"))
      (node (ref "IC2") (pin "8") (pinfunction "VCC_8") (pintype "power_in"))
      (node (ref "JP6") (pin "2") (pinfunction "2_2") (pintype "passive"))
      (node (ref "L1") (pin "2") (pinfunction "2_2") (pintype "passive"))
      (node (ref "L2") (pin "2") (pinfunction "2_2") (pintype "passive"))
      (node (ref "LED2") (pin "A") (pinfunction "A_A") (pintype "passive"))
      (node (ref "LED3") (pin "A") (pinfunction "A_A") (pintype "passive"))
      (node (ref "R2") (pin "2") (pinfunction "2_2") (pintype "passive"))
      (node (ref "R4") (pin "2") (pinfunction "2_2") (pintype "passive"))
      (node (ref "R5") (pin "2") (pinfunction "2_2") (pintype "passive"))
      (node (ref "R6") (pin "2") (pinfunction "2_2") (pintype "passive"))
      (node (ref "R8") (pin "2") (pinfunction "2_2") (pintype "passive"))
      (node (ref "U$1") (pin "16") (pinfunction "VDD_3_16") (pintype "passive"))
      (node (ref "U$1") (pin "2") (pinfunction "VDD_2_2") (pintype "passive"))
      (node (ref "U$1") (pin "30") (pinfunction "AVDD_30") (pintype "passive"))
      (node (ref "U$1") (pin "37") (pinfunction "VDD_4_37") (pintype "passive"))
      (node (ref "U$1") (pin "46") (pinfunction "VDD_5_46") (pintype "passive"))
      (node (ref "U$1") (pin "55") (pinfunction "VUSB_55") (pintype "passive"))
      (node (ref "U$1") (pin "62") (pinfunction "VDD_6_62") (pintype "passive"))
      (node (ref "U$1") (pin "86") (pinfunction "VDD_86") (pintype "passive"))
      (node (ref "U1") (pin "5") (pinfunction "VOUT_5") (pintype "output"))
      (node (ref "U1") (pin "6") (pinfunction "SENSE_6") (pintype "passive"))
      (node (ref "X1") (pin "5") (pinfunction "S_5") (pintype "passive"))
    )
    (net (code "56") (name "VDD5V0_D") (class "Default")
      (node (ref "C18") (pin "1") (pinfunction "1_1") (pintype "passive"))
      (node (ref "C6") (pin "2") (pinfunction "2_2") (pintype "passive"))
      (node (ref "U1") (pin "4") (pinfunction "VIN_4") (pintype "input"))
      (node (ref "U1") (pin "8") (pinfunction "~{SD}_8") (pintype "passive"))
      (node (ref "USB1") (pin "P1") (pinfunction "VUSB_P1") (pintype "bidirectional"))
      (node (ref "X1") (pin "3") (pinfunction "S_3") (pintype "passive"))
    )
    (net (code "57") (name "WR*") (class "Default")
      (node (ref "IC1") (pin "29") (pinfunction "ACBUS3/RXLED#/GPIOH3_29") (pintype "bidirectional"))
      (node (ref "U$1") (pin "81") (pinfunction "OC5/PMWR/CN13/RD4_81") (pintype "passive"))
    )
    (net (code "58") (name "unconnected-(IC1-ACBUS5{slash}GPIOH5-Pad32)") (class "Default")
      (node (ref "IC1") (pin "32") (pinfunction "ACBUS5/GPIOH5_32") (pintype "bidirectional"))
    )
    (net (code "59") (name "unconnected-(IC1-ACBUS6{slash}GPIOH6-Pad33)") (class "Default")
      (node (ref "IC1") (pin "33") (pinfunction "ACBUS6/GPIOH6_33") (pintype "bidirectional"))
    )
    (net (code "60") (name "unconnected-(IC1-ACBUS7{slash}GPIOH7-Pad34)") (class "Default")
      (node (ref "IC1") (pin "34") (pinfunction "ACBUS7/GPIOH7_34") (pintype "bidirectional"))
    )
    (net (code "61") (name "unconnected-(IC1-BCBUS0{slash}GPIOH1-Pad48)") (class "Default")
      (node (ref "IC1") (pin "48") (pinfunction "BCBUS0/GPIOH1_48") (pintype "bidirectional"))
    )
    (net (code "62") (name "unconnected-(IC1-BCBUS1{slash}GPIOH2-Pad52)") (class "Default")
      (node (ref "IC1") (pin "52") (pinfunction "BCBUS1/GPIOH2_52") (pintype "bidirectional"))
    )
    (net (code "63") (name "unconnected-(IC1-BCBUS2-Pad53)") (class "Default")
      (node (ref "IC1") (pin "53") (pinfunction "BCBUS2_53") (pintype "bidirectional"))
    )
    (net (code "64") (name "unconnected-(IC1-BCBUS5{slash}GPIOH5-Pad57)") (class "Default")
      (node (ref "IC1") (pin "57") (pinfunction "BCBUS5/GPIOH5_57") (pintype "bidirectional"))
    )
    (net (code "65") (name "unconnected-(IC1-BCBUS6{slash}GPIOH6-Pad58)") (class "Default")
      (node (ref "IC1") (pin "58") (pinfunction "BCBUS6/GPIOH6_58") (pintype "bidirectional"))
    )
    (net (code "66") (name "unconnected-(IC1-BCBUS7{slash}GPIOH7-Pad59)") (class "Default")
      (node (ref "IC1") (pin "59") (pinfunction "BCBUS7/GPIOH7_59") (pintype "bidirectional"))
    )
    (net (code "67") (name "unconnected-(IC1-BDBUS2{slash}RTS#{slash}TDO{slash}DI-Pad40)") (class "Default")
      (node (ref "IC1") (pin "40") (pinfunction "BDBUS2/RTS#/TDO/DI_40") (pintype "bidirectional"))
    )
    (net (code "68") (name "unconnected-(IC1-BDBUS3{slash}CTS#{slash}TMS{slash}CS-Pad41)") (class "Default")
      (node (ref "IC1") (pin "41") (pinfunction "BDBUS3/CTS#/TMS/CS_41") (pintype "bidirectional"))
    )
    (net (code "69") (name "unconnected-(IC1-BDBUS4{slash}DTR#{slash}GPIOL0-Pad43)") (class "Default")
      (node (ref "IC1") (pin "43") (pinfunction "BDBUS4/DTR#/GPIOL0_43") (pintype "bidirectional"))
    )
    (net (code "70") (name "unconnected-(IC1-BDBUS5{slash}DSR#{slash}GPIOL1-Pad44)") (class "Default")
      (node (ref "IC1") (pin "44") (pinfunction "BDBUS5/DSR#/GPIOL1_44") (pintype "bidirectional"))
    )
    (net (code "71") (name "unconnected-(IC1-BDBUS6{slash}DCD#{slash}GPIOL2-Pad45)") (class "Default")
      (node (ref "IC1") (pin "45") (pinfunction "BDBUS6/DCD#/GPIOL2_45") (pintype "bidirectional"))
    )
    (net (code "72") (name "unconnected-(IC1-BDBUS7{slash}RI#{slash}GPIOL3-Pad46)") (class "Default")
      (node (ref "IC1") (pin "46") (pinfunction "BDBUS7/RI#/GPIOL3_46") (pintype "bidirectional"))
    )
    (net (code "73") (name "unconnected-(IC1-PWREN#-Pad60)") (class "Default")
      (node (ref "IC1") (pin "60") (pinfunction "PWREN#_60") (pintype "bidirectional"))
    )
    (net (code "74") (name "unconnected-(IC1-SUSPEND#-Pad36)") (class "Default")
      (node (ref "IC1") (pin "36") (pinfunction "SUSPEND#_36") (pintype "bidirectional"))
    )
    (net (code "75") (name "unconnected-(JP6-Pad6)") (class "Default")
      (node (ref "JP6") (pin "6") (pinfunction "6_6") (pintype "passive"))
    )
    (net (code "76") (name "unconnected-(U$1-*SS1{slash}IC2{slash}RD9-Pad69)") (class "Default")
      (node (ref "U$1") (pin "69") (pinfunction "*SS1/IC2/RD9_69") (pintype "passive"))
    )
    (net (code "77") (name "unconnected-(U$1-AC1RX{slash}*SS3A{slash}U3BRX{slash}*U3ACTS{slash}RF12-Pad40)") (class "Default")
      (node (ref "U$1") (pin "40") (pinfunction "AC1RX/*SS3A/U3BRX/*U3ACTS/RF12_40") (pintype "passive"))
    )
    (net (code "78") (name "unconnected-(U$1-AC1TX{slash}SCK3A{slash}U3BTX{slash}*U3ARTS{slash}RF13-Pad39)") (class "Default")
      (node (ref "U$1") (pin "39") (pinfunction "AC1TX/SCK3A/U3BTX/*U3ARTS/RF13_39") (pintype "passive"))
    )
    (net (code "79") (name "unconnected-(U$1-AERXD0{slash}INT1{slash}RE8-Pad18)") (class "Default")
      (node (ref "U$1") (pin "18") (pinfunction "AERXD0/INT1/RE8_18") (pintype "passive"))
    )
    (net (code "80") (name "unconnected-(U$1-AERXD1{slash}INT2{slash}RE9-Pad19)") (class "Default")
      (node (ref "U$1") (pin "19") (pinfunction "AERXD1/INT2/RE9_19") (pintype "passive"))
    )
    (net (code "81") (name "unconnected-(U$1-AERXERR{slash}RG15-Pad1)") (class "Default")
      (node (ref "U$1") (pin "1") (pinfunction "AERXERR/RG15_1") (pintype "passive"))
    )
    (net (code "82") (name "unconnected-(U$1-AETXCLK{slash}SCL1{slash}INT3{slash}RA14-Pad66)") (class "Default")
      (node (ref "U$1") (pin "66") (pinfunction "AETXCLK/SCL1/INT3/RA14_66") (pintype "passive"))
    )
    (net (code "83") (name "unconnected-(U$1-AETXD0{slash}*SS1A{slash}U1BRX{slash}*U1ACTS{slash}CN20{slash}RD14-Pad47)") (class "Default")
      (node (ref "U$1") (pin "47") (pinfunction "AETXD0/*SS1A/U1BRX/*U1ACTS/CN20/RD14_47") (pintype "passive"))
    )
    (net (code "84") (name "unconnected-(U$1-AETXD1{slash}SCK1A{slash}U1BTX{slash}*U1ARTS{slash}CN21{slash}RD15-Pad48)") (class "Default")
      (node (ref "U$1") (pin "48") (pinfunction "AETXD1/SCK1A/U1BTX/*U1ARTS/CN21/RD15_48") (pintype "passive"))
    )
    (net (code "85") (name "unconnected-(U$1-AETXEN{slash}SDA1{slash}INT4{slash}RA15-Pad67)") (class "Default")
      (node (ref "U$1") (pin "67") (pinfunction "AETXEN/SDA1/INT4/RA15_67") (pintype "passive"))
    )
    (net (code "86") (name "unconnected-(U$1-AN2{slash}C2IN-{slash}CN4{slash}RB2-Pad23)") (class "Default")
      (node (ref "U$1") (pin "23") (pinfunction "AN2/C2IN-/CN4/RB2_23") (pintype "passive"))
    )
    (net (code "87") (name "unconnected-(U$1-AN3{slash}C2IN+{slash}CN5{slash}RB3-Pad22)") (class "Default")
      (node (ref "U$1") (pin "22") (pinfunction "AN3/C2IN+/CN5/RB3_22") (pintype "passive"))
    )
    (net (code "88") (name "unconnected-(U$1-AN4{slash}C1IN-{slash}CN6{slash}RB4-Pad21)") (class "Default")
      (node (ref "U$1") (pin "21") (pinfunction "AN4/C1IN-/CN6/RB4_21") (pintype "passive"))
    )
    (net (code "89") (name "unconnected-(U$1-AN5{slash}C1IN+{slash}VBUSON{slash}CN7{slash}RB5-Pad20)") (class "Default")
      (node (ref "U$1") (pin "20") (pinfunction "AN5/C1IN+/VBUSON/CN7/RB5_20") (pintype "passive"))
    )
    (net (code "90") (name "unconnected-(U$1-AN8{slash}C1OUT{slash}RB8-Pad32)") (class "Default")
      (node (ref "U$1") (pin "32") (pinfunction "AN8/C1OUT/RB8_32") (pintype "passive"))
    )
    (net (code "91") (name "unconnected-(U$1-AN9{slash}C2OUT{slash}RB9-Pad33)") (class "Default")
      (node (ref "U$1") (pin "33") (pinfunction "AN9/C2OUT/RB9_33") (pintype "passive"))
    )
    (net (code "92") (name "unconnected-(U$1-AN10{slash}CVREFOUT{slash}PMA13{slash}RB10-Pad34)") (class "Default")
      (node (ref "U$1") (pin "34") (pinfunction "AN10/CVREFOUT/PMA13/RB10_34") (pintype "passive"))
    )
    (net (code "93") (name "unconnected-(U$1-AN11{slash}ERXERR{slash}AETXERR{slash}PMA12{slash}RB11-Pad35)") (class "Default")
      (node (ref "U$1") (pin "35") (pinfunction "AN11/ERXERR/AETXERR/PMA12/RB11_35") (pintype "passive"))
    )
    (net (code "94") (name "unconnected-(U$1-AN12{slash}ERXD0{slash}AECRS{slash}PMA11{slash}RB12-Pad41)") (class "Default")
      (node (ref "U$1") (pin "41") (pinfunction "AN12/ERXD0/AECRS/PMA11/RB12_41") (pintype "passive"))
    )
    (net (code "95") (name "unconnected-(U$1-AN13{slash}ERXD1{slash}AECOL{slash}PMA10{slash}RB13-Pad42)") (class "Default")
      (node (ref "U$1") (pin "42") (pinfunction "AN13/ERXD1/AECOL/PMA10/RB13_42") (pintype "passive"))
    )
    (net (code "96") (name "unconnected-(U$1-AN14{slash}ERXD2{slash}AETXD3{slash}PMALH{slash}PMA1{slash}RB14-Pad43)") (class "Default")
      (node (ref "U$1") (pin "43") (pinfunction "AN14/ERXD2/AETXD3/PMALH/PMA1/RB14_43") (pintype "passive"))
    )
    (net (code "97") (name "unconnected-(U$1-C2RX{slash}PMD8{slash}RG0-Pad90)") (class "Default")
      (node (ref "U$1") (pin "90") (pinfunction "C2RX/PMD8/RG0_90") (pintype "passive"))
    )
    (net (code "98") (name "unconnected-(U$1-C2TX{slash}ETXERR{slash}PMD9{slash}RG1-Pad89)") (class "Default")
      (node (ref "U$1") (pin "89") (pinfunction "C2TX/ETXERR/PMD9/RG1_89") (pintype "passive"))
    )
    (net (code "99") (name "unconnected-(U$1-D+{slash}RG2-Pad57)") (class "Default")
      (node (ref "U$1") (pin "57") (pinfunction "D+/RG2_57") (pintype "passive"))
    )
    (net (code "100") (name "unconnected-(U$1-D-{slash}RG3-Pad56)") (class "Default")
      (node (ref "U$1") (pin "56") (pinfunction "D-/RG3_56") (pintype "passive"))
    )
    (net (code "101") (name "unconnected-(U$1-ECOL{slash}SCK2A{slash}U2BTX{slash}*U2ARTS{slash}PMA5{slash}CN8{slash}RG6-Pad10)") (class "Default")
      (node (ref "U$1") (pin "10") (pinfunction "ECOL/SCK2A/U2BTX/*U2ARTS/PMA5/CN8/RG6_10") (pintype "passive"))
    )
    (net (code "102") (name "unconnected-(U$1-ERXCLK{slash}*SS2A{slash}U2BRX{slash}*U2ACTS{slash}PMA2{slash}CN11{slash}RG9-Pad14)") (class "Default")
      (node (ref "U$1") (pin "14") (pinfunction "ERXCLK/*SS2A/U2BRX/*U2ACTS/PMA2/CN11/RG9_14") (pintype "passive"))
    )
    (net (code "103") (name "unconnected-(U$1-ETXCLK{slash}PMD15{slash}CN16{slash}RD7-Pad84)") (class "Default")
      (node (ref "U$1") (pin "84") (pinfunction "ETXCLK/PMD15/CN16/RD7_84") (pintype "passive"))
    )
    (net (code "104") (name "unconnected-(U$1-ETXD2{slash}IC5{slash}PMD12{slash}RD12-Pad79)") (class "Default")
      (node (ref "U$1") (pin "79") (pinfunction "ETXD2/IC5/PMD12/RD12_79") (pintype "passive"))
    )
    (net (code "105") (name "unconnected-(U$1-ETXD3{slash}PMD13{slash}CN19{slash}RD13-Pad80)") (class "Default")
      (node (ref "U$1") (pin "80") (pinfunction "ETXD3/PMD13/CN19/RD13_80") (pintype "passive"))
    )
    (net (code "106") (name "unconnected-(U$1-ETXEN{slash}PMD14{slash}CN15{slash}RD6-Pad83)") (class "Default")
      (node (ref "U$1") (pin "83") (pinfunction "ETXEN/PMD14/CN15/RD6_83") (pintype "passive"))
    )
    (net (code "107") (name "unconnected-(U$1-OC2{slash}RD1-Pad76)") (class "Default")
      (node (ref "U$1") (pin "76") (pinfunction "OC2/RD1_76") (pintype "passive"))
    )
    (net (code "108") (name "unconnected-(U$1-OC3{slash}RD2-Pad77)") (class "Default")
      (node (ref "U$1") (pin "77") (pinfunction "OC3/RD2_77") (pintype "passive"))
    )
    (net (code "109") (name "unconnected-(U$1-OC4{slash}RD3-Pad78)") (class "Default")
      (node (ref "U$1") (pin "78") (pinfunction "OC4/RD3_78") (pintype "passive"))
    )
    (net (code "110") (name "unconnected-(U$1-PGED2{slash}AN7{slash}RB7-Pad27)") (class "Default")
      (node (ref "U$1") (pin "27") (pinfunction "PGED2/AN7/RB7_27") (pintype "passive"))
    )
    (net (code "111") (name "unconnected-(U$1-RTCC{slash}EMDIO{slash}IC1{slash}RD8-Pad68)") (class "Default")
      (node (ref "U$1") (pin "68") (pinfunction "RTCC/EMDIO/IC1/RD8_68") (pintype "passive"))
    )
    (net (code "112") (name "unconnected-(U$1-SOSCI{slash}CN1{slash}RC13-Pad73)") (class "Default")
      (node (ref "U$1") (pin "73") (pinfunction "SOSCI/CN1/RC13_73") (pintype "passive"))
    )
    (net (code "113") (name "unconnected-(U$1-SOSCO{slash}T1CK{slash}CN0{slash}RC14-Pad74)") (class "Default")
      (node (ref "U$1") (pin "74") (pinfunction "SOSCO/T1CK/CN0/RC14_74") (pintype "passive"))
    )
    (net (code "114") (name "unconnected-(U$1-T2CK{slash}RC1-Pad6)") (class "Default")
      (node (ref "U$1") (pin "6") (pinfunction "T2CK/RC1_6") (pintype "passive"))
    )
    (net (code "115") (name "unconnected-(U$1-T3CK{slash}RC2-Pad7)") (class "Default")
      (node (ref "U$1") (pin "7") (pinfunction "T3CK/RC2_7") (pintype "passive"))
    )
    (net (code "116") (name "unconnected-(U$1-TCK{slash}RA1-Pad38)") (class "Default")
      (node (ref "U$1") (pin "38") (pinfunction "TCK/RA1_38") (pintype "passive"))
    )
    (net (code "117") (name "unconnected-(U$1-TDI{slash}RA4-Pad60)") (class "Default")
      (node (ref "U$1") (pin "60") (pinfunction "TDI/RA4_60") (pintype "passive"))
    )
    (net (code "118") (name "unconnected-(U$1-TDO{slash}RA5-Pad61)") (class "Default")
      (node (ref "U$1") (pin "61") (pinfunction "TDO/RA5_61") (pintype "passive"))
    )
    (net (code "119") (name "unconnected-(U$1-TMS{slash}RA0-Pad17)") (class "Default")
      (node (ref "U$1") (pin "17") (pinfunction "TMS/RA0_17") (pintype "passive"))
    )
    (net (code "120") (name "unconnected-(U$1-TRCLK{slash}RA6-Pad91)") (class "Default")
      (node (ref "U$1") (pin "91") (pinfunction "TRCLK/RA6_91") (pintype "passive"))
    )
    (net (code "121") (name "unconnected-(U$1-TRD0{slash}RG13-Pad97)") (class "Default")
      (node (ref "U$1") (pin "97") (pinfunction "TRD0/RG13_97") (pintype "passive"))
    )
    (net (code "122") (name "unconnected-(U$1-TRD1{slash}RG12-Pad96)") (class "Default")
      (node (ref "U$1") (pin "96") (pinfunction "TRD1/RG12_96") (pintype "passive"))
    )
    (net (code "123") (name "unconnected-(U$1-TRD2{slash}RG14-Pad95)") (class "Default")
      (node (ref "U$1") (pin "95") (pinfunction "TRD2/RG14_95") (pintype "passive"))
    )
    (net (code "124") (name "unconnected-(U$1-TRD3{slash}RA7-Pad92)") (class "Default")
      (node (ref "U$1") (pin "92") (pinfunction "TRD3/RA7_92") (pintype "passive"))
    )
    (net (code "125") (name "unconnected-(U$1-USBID{slash}RF3-Pad51)") (class "Default")
      (node (ref "U$1") (pin "51") (pinfunction "USBID/RF3_51") (pintype "passive"))
    )
    (net (code "126") (name "unconnected-(U$1-VBUS-Pad54)") (class "Default")
      (node (ref "U$1") (pin "54") (pinfunction "VBUS_54") (pintype "passive"))
    )
    (net (code "127") (name "unconnected-(U$1-VREF+{slash}CVREF+{slash}AERXD3{slash}PMA6{slash}RA10-Pad29)") (class "Default")
      (node (ref "U$1") (pin "29") (pinfunction "VREF+/CVREF+/AERXD3/PMA6/RA10_29") (pintype "passive"))
    )
    (net (code "128") (name "unconnected-(U$1-VREF-{slash}CVREF-{slash}AERXD2{slash}PMA7{slash}RA9-Pad28)") (class "Default")
      (node (ref "U$1") (pin "28") (pinfunction "VREF-/CVREF-/AERXD2/PMA7/RA9_28") (pintype "passive"))
    )
    (net (code "129") (name "unconnected-(U1-NC-Pad2)") (class "Default")
      (node (ref "U1") (pin "2") (pinfunction "NC_2") (pintype "passive"))
    )
    (net (code "130") (name "unconnected-(U1-~{ERROR}-Pad7)") (class "Default")
      (node (ref "U1") (pin "7") (pinfunction "~{ERROR}_7") (pintype "passive"))
    )
    (net (code "131") (name "unconnected-(USB1B-USBID-PadP4)") (class "Default")
      (node (ref "USB1") (pin "P4") (pinfunction "USBID_P4") (pintype "bidirectional"))
    )
    (net (code "132") (name "unconnected-(X1AB-S-Pad7)") (class "Default")
      (node (ref "X1") (pin "7") (pinfunction "S_7") (pintype "passive"))
    )
    (net (code "133") (name "unconnected-(X1AD-S-Pad9)") (class "Default")
      (node (ref "X1") (pin "9") (pinfunction "S_9") (pintype "passive"))
    )
    (net (code "134") (name "unconnected-(X1C-S-Pad11)") (class "Default")
      (node (ref "X1") (pin "11") (pinfunction "S_11") (pintype "passive"))
    )
    (net (code "135") (name "unconnected-(X1E-S-Pad13)") (class "Default")
      (node (ref "X1") (pin "13") (pinfunction "S_13") (pintype "passive"))
    )
    (net (code "136") (name "unconnected-(X1G-S-Pad15)") (class "Default")
      (node (ref "X1") (pin "15") (pinfunction "S_15") (pintype "passive"))
    )
    (net (code "137") (name "unconnected-(X1I-S-Pad17)") (class "Default")
      (node (ref "X1") (pin "17") (pinfunction "S_17") (pintype "passive"))
    )
    (net (code "138") (name "unconnected-(X1K-S-Pad19)") (class "Default")
      (node (ref "X1") (pin "19") (pinfunction "S_19") (pintype "passive"))
    )
    (net (code "139") (name "unconnected-(X1N-S-Pad21)") (class "Default")
      (node (ref "X1") (pin "21") (pinfunction "S_21") (pintype "passive"))
    )
    (net (code "140") (name "unconnected-(X1P-S-Pad23)") (class "Default")
      (node (ref "X1") (pin "23") (pinfunction "S_23") (pintype "passive"))
    )
    (net (code "141") (name "unconnected-(X1R-S-Pad25)") (class "Default")
      (node (ref "X1") (pin "25") (pinfunction "S_25") (pintype "passive"))
    )
    (net (code "142") (name "unconnected-(X1T-S-Pad27)") (class "Default")
      (node (ref "X1") (pin "27") (pinfunction "S_27") (pintype "passive"))
    )
  )
)
